# TopSheet.net
KiCad netlist of a schematic drawn in Altium Designer
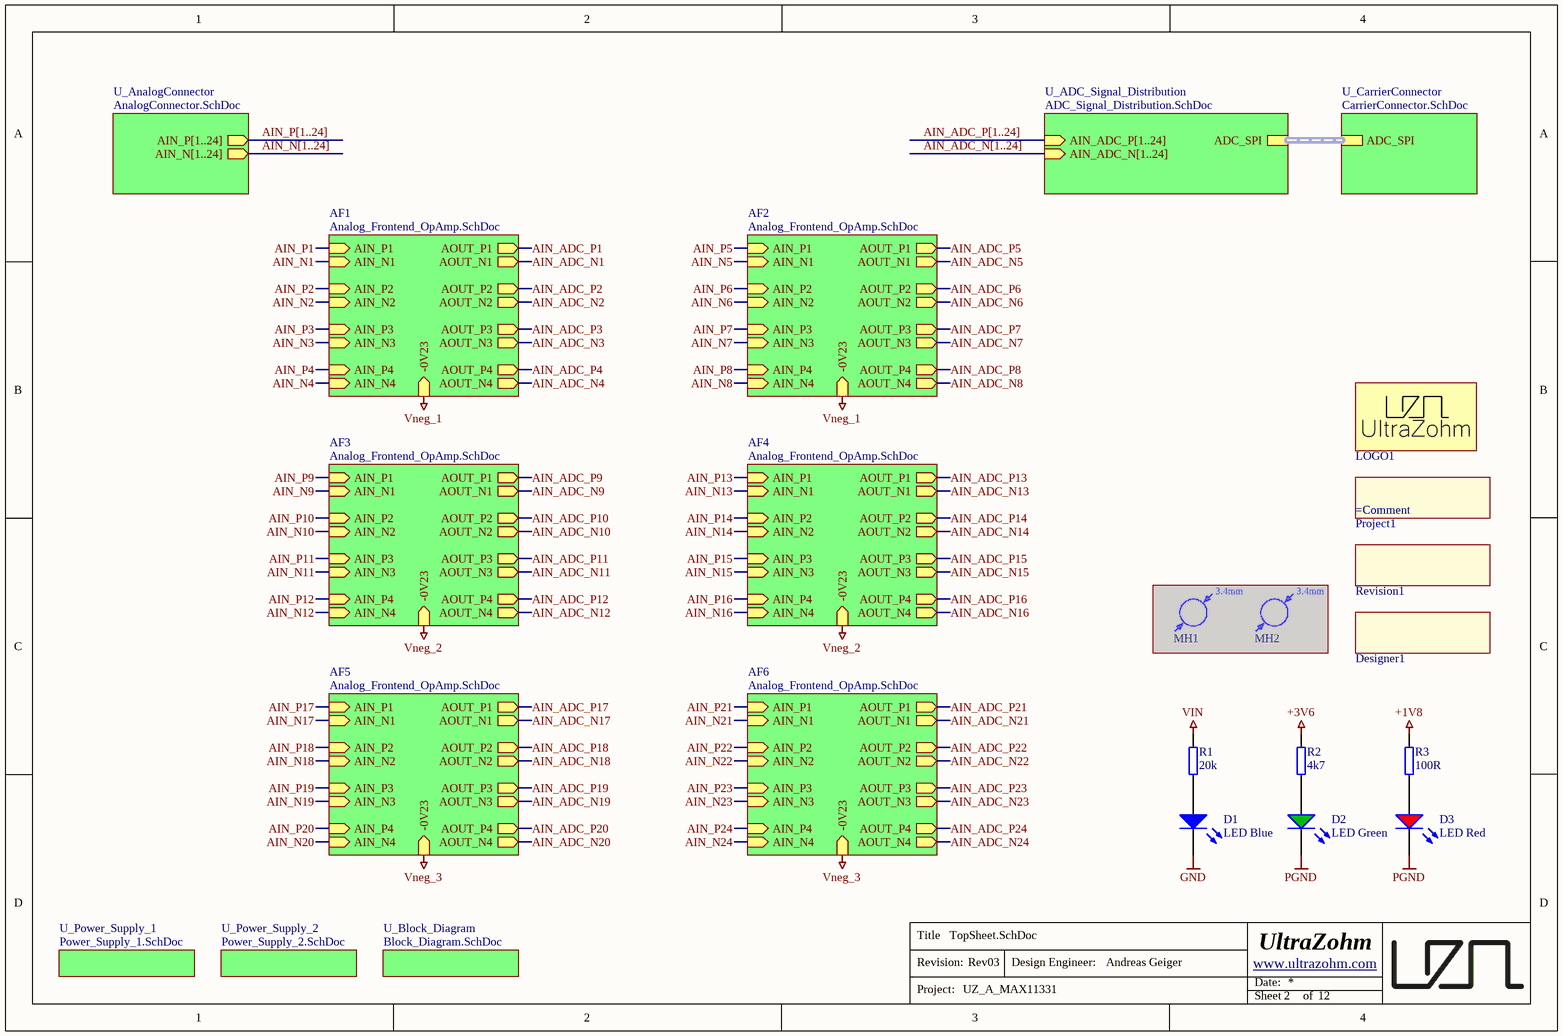
[diagram p0: TopSheet.SchDoc]

(export (version "E")
  (design (tool "Eeschema 10.0.6"))
  (components
    (comp (ref "D1")
      (value "LED Blue")
      (footprint "WL-SMCW_0603")
      (description "LED BLUE 465~475NM 11.5~28.5MCD@5MA TOP VIEW 0603 ROHS")
      (fields
        (field (name "MANUFACTURER PART NUMBER") "19-217/BHC-ZL1M2RY/3T")
        (field (name "MANUFACTURER") "Everlight Elec")
        (field (name "CREATED FROM") "T. Wendt")
      )
      (libsource (lib "user") (part "LED_Blue"))
    )
    (comp (ref "D2")
      (value "LED Green")
      (footprint "WL-SMCW_0603")
      (description "LED GREEN 520~535NM 112~258MCD@20MA TOP VIEW 0603 ROHS")
      (fields
        (field (name "MANUFACTURER PART NUMBER") "19-217/GHC-YR1S2/3T")
        (field (name "MANUFACTURER") "Everlight Elec")
        (field (name "CREATED FROM") "T. Wendt")
      )
      (libsource (lib "user") (part "LED_Green"))
    )
    (comp (ref "D3")
      (value "LED Red")
      (footprint "WL-SMCW_0603")
      (description "LED RED 520~625NM 90~100MCD@20MA TOP VIEW 0603 ROHS")
      (fields
        (field (name "MANUFACTURER PART NUMBER") "KT-0603R")
        (field (name "MANUFACTURER") "Hubei KENTO Elec")
        (field (name "CREATED FROM") "T. Wendt")
      )
      (libsource (lib "user") (part "LED_Red"))
    )
    (comp (ref "Designer1")
      (value "~")
      (footprint "Designator:comment")
      (fields
        (field (name "MANUFACTURER") "PCB Manufacturer")
        (field (name "MANUFACTURER PART NUMBER") "Project Author")
        (field (name "CREATED FROM") "T. Wendt")
      )
      (libsource (lib "user") (part "ProjectAuthor"))
    )
    (comp (ref "LOGO1")
      (value "UZ Logo")
      (footprint "UZ_Logo_small")
      (description "Official Project Logo of the UltraZohm")
      (fields
        (field (name "MANUFACTURER") "PCB Manufacturer")
        (field (name "MANUFACTURER PART NUMBER") "UltraZohm Logo")
        (field (name "CREATED FROM") "T. Wendt")
      )
      (libsource (lib "user") (part "UZ_LOGO"))
    )
    (comp (ref "MH1")
      (value "mounting hole 3,4mm")
      (footprint "MH_3.4")
      (description "Non plated through hole, 3.4mm")
      (libsource (lib "UltraZohm_ADC") (part "Mounting Hole"))
    )
    (comp (ref "MH2")
      (value "mounting hole 3,4mm")
      (footprint "MH_3.4")
      (description "Non plated through hole, 3.4mm")
      (libsource (lib "UltraZohm_ADC") (part "Mounting Hole"))
    )
    (comp (ref "Project1")
      (value "~")
      (footprint "COMMENT")
      (fields
        (field (name "MANUFACTURER") "PCB Manufacturer")
        (field (name "MANUFACTURER PART NUMBER") "Project Name")
        (field (name "CREATED FROM") "T. Wendt")
      )
      (libsource (lib "user") (part "ProjectName"))
    )
    (comp (ref "R1")
      (value "20k")
      (footprint "RES 0603_1608")
      (description "SMD resistor E24 series")
      (fields
        (field (name "MANUFACTURER PART NUMBER") "0603WAF2002T5E")
        (field (name "MANUFACTURER") "UNI-ROYAL")
        (field (name "CREATED FROM") "AGeiger")
      )
      (libsource (lib "user") (part "Resistor"))
    )
    (comp (ref "R2")
      (value "4k7")
      (footprint "R_0603_TE")
      (description "Generic resistor")
      (fields
        (field (name "MANUFACTURER PART NUMBER") "UZgen_R_0603_4k7")
        (field (name "MANUFACTURER") "UZgen")
        (field (name "CREATED FROM") "UZgenTool")
      )
      (libsource (lib "user") (part "RES"))
    )
    (comp (ref "R3")
      (value "100R")
      (footprint "RES 0603_1608")
      (description "SMD resistor E24 series")
      (fields
        (field (name "MANUFACTURER PART NUMBER") "RK73B1JTTD101J")
        (field (name "MANUFACTURER") "KOA Speer")
        (field (name "CREATED FROM") "MGremer")
      )
      (libsource (lib "user") (part "Resistor"))
    )
    (comp (ref "Revision1")
      (value "~")
      (footprint "Designator:comment")
      (fields
        (field (name "MANUFACTURER") "PCB Manufacturer")
        (field (name "MANUFACTURER PART NUMBER") "Project Revision")
        (field (name "CREATED FROM") "T. Wendt")
      )
      (libsource (lib "user") (part "ProjectRevision"))
    )
  )
  (nets
    (net (code "1") (name "+1V8") (class "Default")
      (node (ref "R3") (pin "2") (pinfunction "2_2") (pintype "passive"))
    )
    (net (code "2") (name "+3V6") (class "Default")
      (node (ref "R2") (pin "2") (pinfunction "2_2") (pintype "passive"))
    )
    (net (code "104") (name "GND") (class "Default")
      (node (ref "D1") (pin "1") (pinfunction "K_1") (pintype "passive"))
    )
    (net (code "105") (name "Net-(D1-A)") (class "Default")
      (node (ref "D1") (pin "2") (pinfunction "A_2") (pintype "passive"))
      (node (ref "R1") (pin "1") (pinfunction "1_1") (pintype "passive"))
    )
    (net (code "106") (name "Net-(D2-A)") (class "Default")
      (node (ref "D2") (pin "2") (pinfunction "A_2") (pintype "passive"))
      (node (ref "R2") (pin "1") (pinfunction "1_1") (pintype "passive"))
    )
    (net (code "107") (name "Net-(D3-A)") (class "Default")
      (node (ref "D3") (pin "2") (pinfunction "A_2") (pintype "passive"))
      (node (ref "R3") (pin "1") (pinfunction "1_1") (pintype "passive"))
    )
    (net (code "108") (name "PGND") (class "Default")
      (node (ref "D2") (pin "1") (pinfunction "K_1") (pintype "passive"))
      (node (ref "D3") (pin "1") (pinfunction "K_1") (pintype "passive"))
    )
    (net (code "109") (name "VIN") (class "Default")
      (node (ref "R1") (pin "2") (pinfunction "2_2") (pintype "passive"))
    )
  )
)
